# ME433.net
KiCad netlist of a schematic drawn in EAGLE
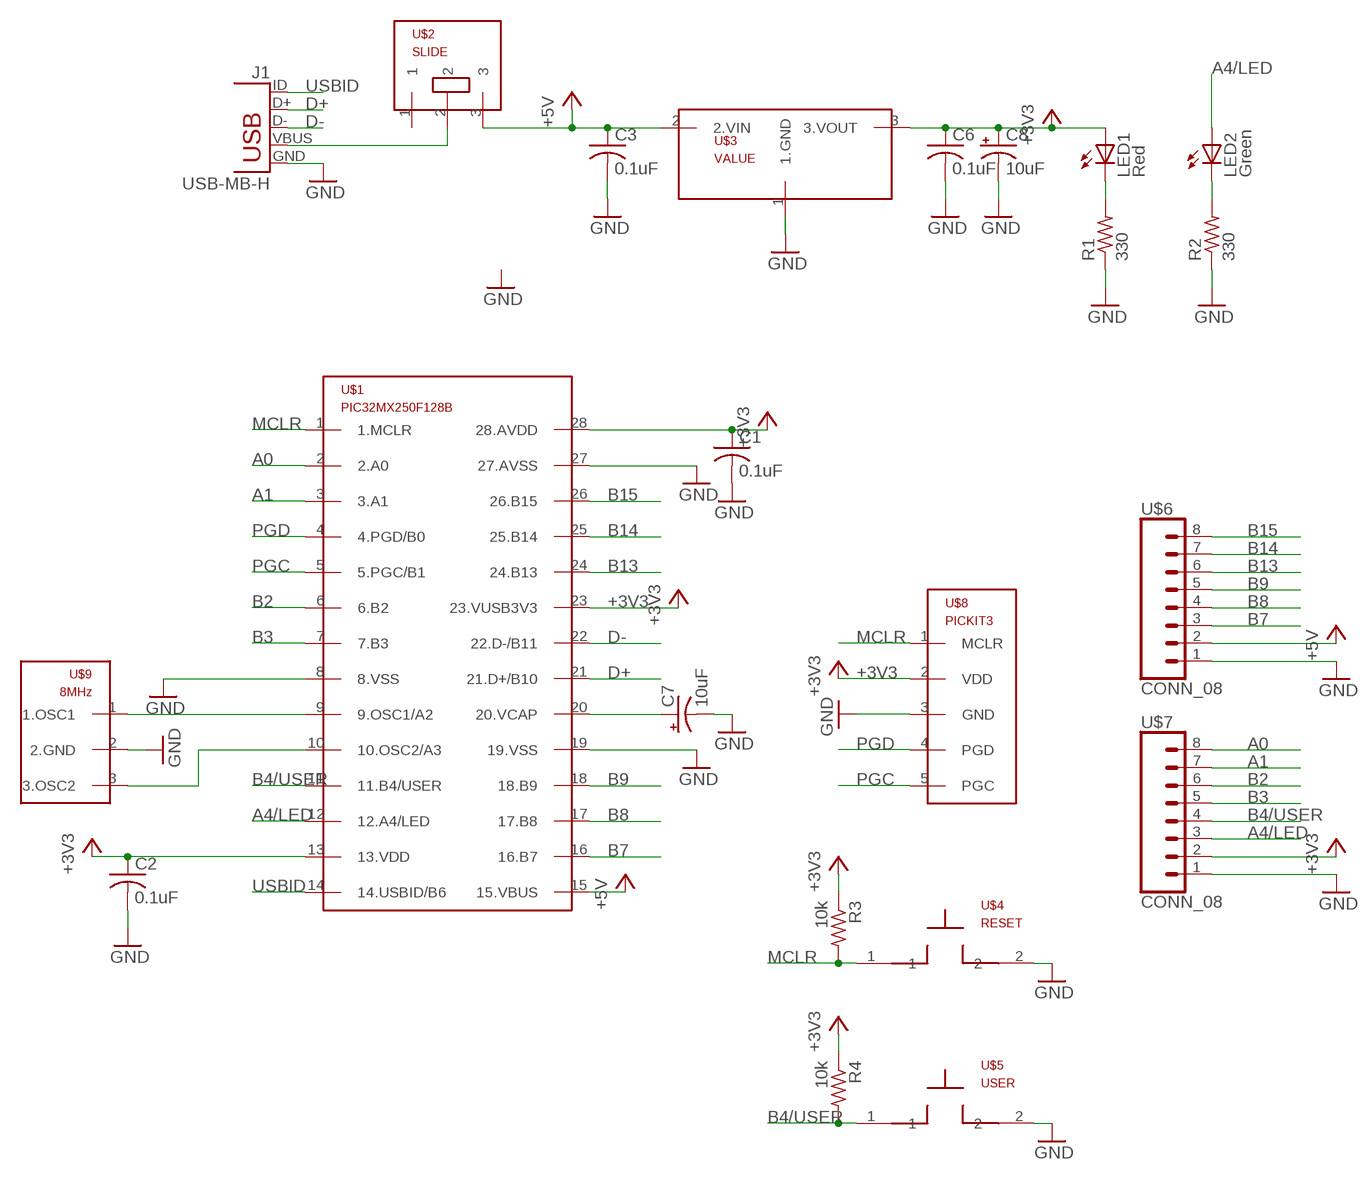
[diagram p0: schematic, sheet 1]

(export (version "E")
  (design (tool "Eeschema 10.0.6"))
  (components
    (comp (ref "C1")
      (value "0.1uF")
      (footprint "eagle-import:C025-025X050")
      (libsource (lib "eagle-import") (part "C-US025-025X050"))
    )
    (comp (ref "C2")
      (value "0.1uF")
      (footprint "eagle-import:C025-025X050")
      (libsource (lib "eagle-import") (part "C-US025-025X050"))
    )
    (comp (ref "C3")
      (value "0.1uF")
      (footprint "eagle-import:C025-025X050")
      (libsource (lib "eagle-import") (part "C-US025-025X050"))
    )
    (comp (ref "C6")
      (value "0.1uF")
      (footprint "eagle-import:C025-025X050")
      (libsource (lib "eagle-import") (part "C-US025-025X050"))
    )
    (comp (ref "C7")
      (value "10uF")
      (footprint "eagle-import:B45181B")
      (libsource (lib "eagle-import") (part "CPOL-USB45181B"))
    )
    (comp (ref "C8")
      (value "10uF")
      (footprint "eagle-import:B45181B")
      (libsource (lib "eagle-import") (part "CPOL-USB45181B"))
    )
    (comp (ref "J1")
      (value "USB-MB-H")
      (footprint "eagle-import:USB-MB-H")
      (libsource (lib "eagle-import") (part "USB-MB-H"))
    )
    (comp (ref "LED1")
      (value "Red")
      (footprint "eagle-import:LED3MM")
      (libsource (lib "eagle-import") (part "LED3MM"))
    )
    (comp (ref "LED2")
      (value "Green")
      (footprint "eagle-import:LED3MM")
      (libsource (lib "eagle-import") (part "LED3MM"))
    )
    (comp (ref "R1")
      (value "330")
      (footprint "eagle-import:0207_10")
      (libsource (lib "eagle-import") (part "R-US_0207/10"))
    )
    (comp (ref "R2")
      (value "330")
      (footprint "eagle-import:0207_10")
      (libsource (lib "eagle-import") (part "R-US_0207/10"))
    )
    (comp (ref "R3")
      (value "10k")
      (footprint "eagle-import:0207_10")
      (libsource (lib "eagle-import") (part "R-US_0207/10"))
    )
    (comp (ref "R4")
      (value "10k")
      (footprint "eagle-import:0207_10")
      (libsource (lib "eagle-import") (part "R-US_0207/10"))
    )
    (comp (ref "U$1")
      (value "PIC32MX250F128B")
      (footprint "eagle-import:DIL28-3")
      (libsource (lib "eagle-import") (part "PIC32MX250F128B"))
    )
    (comp (ref "U$2")
      (value "SLIDE")
      (footprint "eagle-import:SLIDE")
      (libsource (lib "eagle-import") (part "SLIDE"))
    )
    (comp (ref "U$3")
      (value "MCP1702")
      (footprint "eagle-import:TO92")
      (libsource (lib "eagle-import") (part "MCP1702"))
    )
    (comp (ref "U$4")
      (value "RESET")
      (footprint "eagle-import:PB")
      (libsource (lib "eagle-import") (part "PB"))
    )
    (comp (ref "U$5")
      (value "USER")
      (footprint "eagle-import:PB")
      (libsource (lib "eagle-import") (part "PB"))
    )
    (comp (ref "U$6")
      (value "CONN_08")
      (footprint "eagle-import:1X08")
      (libsource (lib "eagle-import") (part "CONN_08"))
    )
    (comp (ref "U$7")
      (value "CONN_08")
      (footprint "eagle-import:1X08")
      (libsource (lib "eagle-import") (part "CONN_08"))
    )
    (comp (ref "U$8")
      (value "PICKIT3")
      (footprint "eagle-import:1X05")
      (libsource (lib "eagle-import") (part "PICKIT3"))
    )
    (comp (ref "U$9")
      (value "8MHz")
      (footprint "eagle-import:OSC")
      (libsource (lib "eagle-import") (part "OSC"))
    )
  )
  (nets
    (net (code "1") (name "+3V3") (class "Default")
      (node (ref "C1") (pin "1") (pinfunction "1_1") (pintype "passive"))
      (node (ref "C2") (pin "1") (pinfunction "1_1") (pintype "passive"))
      (node (ref "C6") (pin "1") (pinfunction "1_1") (pintype "passive"))
      (node (ref "C8") (pin "+") (pinfunction "+_+") (pintype "passive"))
      (node (ref "LED1") (pin "A") (pinfunction "A_A") (pintype "passive"))
      (node (ref "R3") (pin "1") (pinfunction "1_1") (pintype "passive"))
      (node (ref "R4") (pin "1") (pinfunction "1_1") (pintype "passive"))
      (node (ref "U$1") (pin "13") (pinfunction "13.VDD_13") (pintype "bidirectional"))
      (node (ref "U$1") (pin "23") (pinfunction "23.VUSB3V3_23") (pintype "bidirectional"))
      (node (ref "U$1") (pin "28") (pinfunction "28.AVDD_28") (pintype "bidirectional"))
      (node (ref "U$3") (pin "3") (pinfunction "3.VOUT_3") (pintype "bidirectional"))
      (node (ref "U$7") (pin "2") (pinfunction "2_2") (pintype "passive"))
      (node (ref "U$8") (pin "2") (pinfunction "VDD_2") (pintype "bidirectional"))
    )
    (net (code "2") (name "+5V") (class "Default")
      (node (ref "C3") (pin "1") (pinfunction "1_1") (pintype "passive"))
      (node (ref "U$1") (pin "15") (pinfunction "15.VBUS_15") (pintype "bidirectional"))
      (node (ref "U$2") (pin "3") (pinfunction "3_3") (pintype "bidirectional"))
      (node (ref "U$3") (pin "2") (pinfunction "2.VIN_2") (pintype "bidirectional"))
      (node (ref "U$6") (pin "2") (pinfunction "2_2") (pintype "passive"))
    )
    (net (code "3") (name "/A0") (class "Default")
      (node (ref "U$1") (pin "2") (pinfunction "2.A0_2") (pintype "bidirectional"))
      (node (ref "U$7") (pin "8") (pinfunction "8_8") (pintype "passive"))
    )
    (net (code "4") (name "/A1") (class "Default")
      (node (ref "U$1") (pin "3") (pinfunction "3.A1_3") (pintype "bidirectional"))
      (node (ref "U$7") (pin "7") (pinfunction "7_7") (pintype "passive"))
    )
    (net (code "5") (name "/A4{slash}LED") (class "Default")
      (node (ref "LED2") (pin "A") (pinfunction "A_A") (pintype "passive"))
      (node (ref "U$1") (pin "12") (pinfunction "12.A4/LED_12") (pintype "bidirectional"))
      (node (ref "U$7") (pin "3") (pinfunction "3_3") (pintype "passive"))
    )
    (net (code "6") (name "/B2") (class "Default")
      (node (ref "U$1") (pin "6") (pinfunction "6.B2_6") (pintype "bidirectional"))
      (node (ref "U$7") (pin "6") (pinfunction "6_6") (pintype "passive"))
    )
    (net (code "7") (name "/B3") (class "Default")
      (node (ref "U$1") (pin "7") (pinfunction "7.B3_7") (pintype "bidirectional"))
      (node (ref "U$7") (pin "5") (pinfunction "5_5") (pintype "passive"))
    )
    (net (code "8") (name "/B4{slash}USER") (class "Default")
      (node (ref "R4") (pin "2") (pinfunction "2_2") (pintype "passive"))
      (node (ref "U$1") (pin "11") (pinfunction "11.B4/USER_11") (pintype "bidirectional"))
      (node (ref "U$5") (pin "1") (pinfunction "1_1") (pintype "bidirectional"))
      (node (ref "U$7") (pin "4") (pinfunction "4_4") (pintype "passive"))
    )
    (net (code "9") (name "/B7") (class "Default")
      (node (ref "U$1") (pin "16") (pinfunction "16.B7_16") (pintype "bidirectional"))
      (node (ref "U$6") (pin "3") (pinfunction "3_3") (pintype "passive"))
    )
    (net (code "10") (name "/B8") (class "Default")
      (node (ref "U$1") (pin "17") (pinfunction "17.B8_17") (pintype "bidirectional"))
      (node (ref "U$6") (pin "4") (pinfunction "4_4") (pintype "passive"))
    )
    (net (code "11") (name "/B9") (class "Default")
      (node (ref "U$1") (pin "18") (pinfunction "18.B9_18") (pintype "bidirectional"))
      (node (ref "U$6") (pin "5") (pinfunction "5_5") (pintype "passive"))
    )
    (net (code "12") (name "/B13") (class "Default")
      (node (ref "U$1") (pin "24") (pinfunction "24.B13_24") (pintype "bidirectional"))
      (node (ref "U$6") (pin "6") (pinfunction "6_6") (pintype "passive"))
    )
    (net (code "13") (name "/B14") (class "Default")
      (node (ref "U$1") (pin "25") (pinfunction "25.B14_25") (pintype "bidirectional"))
      (node (ref "U$6") (pin "7") (pinfunction "7_7") (pintype "passive"))
    )
    (net (code "14") (name "/B15") (class "Default")
      (node (ref "U$1") (pin "26") (pinfunction "26.B15_26") (pintype "bidirectional"))
      (node (ref "U$6") (pin "8") (pinfunction "8_8") (pintype "passive"))
    )
    (net (code "15") (name "/D+") (class "Default")
      (node (ref "J1") (pin "D+") (pinfunction "D+_D+") (pintype "bidirectional"))
      (node (ref "U$1") (pin "21") (pinfunction "21.D+/B10_21") (pintype "bidirectional"))
    )
    (net (code "16") (name "/D-") (class "Default")
      (node (ref "J1") (pin "D-") (pinfunction "D-_D-") (pintype "bidirectional"))
      (node (ref "U$1") (pin "22") (pinfunction "22.D-/B11_22") (pintype "bidirectional"))
    )
    (net (code "17") (name "/MCLR") (class "Default")
      (node (ref "R3") (pin "2") (pinfunction "2_2") (pintype "passive"))
      (node (ref "U$1") (pin "1") (pinfunction "1.MCLR_1") (pintype "bidirectional"))
      (node (ref "U$4") (pin "1") (pinfunction "1_1") (pintype "bidirectional"))
      (node (ref "U$8") (pin "1") (pinfunction "MCLR_1") (pintype "bidirectional"))
    )
    (net (code "18") (name "/PGC") (class "Default")
      (node (ref "U$1") (pin "5") (pinfunction "5.PGC/B1_5") (pintype "bidirectional"))
      (node (ref "U$8") (pin "5") (pinfunction "PGC_5") (pintype "bidirectional"))
    )
    (net (code "19") (name "/PGD") (class "Default")
      (node (ref "U$1") (pin "4") (pinfunction "4.PGD/B0_4") (pintype "bidirectional"))
      (node (ref "U$8") (pin "4") (pinfunction "PGD_4") (pintype "bidirectional"))
    )
    (net (code "20") (name "/USBID") (class "Default")
      (node (ref "J1") (pin "ID") (pinfunction "D+1_ID") (pintype "bidirectional"))
      (node (ref "U$1") (pin "14") (pinfunction "14.USBID/B6_14") (pintype "bidirectional"))
    )
    (net (code "21") (name "GND") (class "Default")
      (node (ref "C1") (pin "2") (pinfunction "2_2") (pintype "passive"))
      (node (ref "C2") (pin "2") (pinfunction "2_2") (pintype "passive"))
      (node (ref "C3") (pin "2") (pinfunction "2_2") (pintype "passive"))
      (node (ref "C6") (pin "2") (pinfunction "2_2") (pintype "passive"))
      (node (ref "C7") (pin "-") (pinfunction "-_-") (pintype "passive"))
      (node (ref "C8") (pin "-") (pinfunction "-_-") (pintype "passive"))
      (node (ref "J1") (pin "GND") (pinfunction "GND_GND") (pintype "bidirectional"))
      (node (ref "R1") (pin "1") (pinfunction "1_1") (pintype "passive"))
      (node (ref "R2") (pin "1") (pinfunction "1_1") (pintype "passive"))
      (node (ref "U$1") (pin "19") (pinfunction "19.VSS_19") (pintype "bidirectional"))
      (node (ref "U$1") (pin "27") (pinfunction "27.AVSS_27") (pintype "bidirectional"))
      (node (ref "U$1") (pin "8") (pinfunction "8.VSS_8") (pintype "bidirectional"))
      (node (ref "U$3") (pin "1") (pinfunction "1.GND_1") (pintype "bidirectional"))
      (node (ref "U$4") (pin "2") (pinfunction "2_2") (pintype "bidirectional"))
      (node (ref "U$5") (pin "2") (pinfunction "2_2") (pintype "bidirectional"))
      (node (ref "U$6") (pin "1") (pinfunction "1_1") (pintype "passive"))
      (node (ref "U$7") (pin "1") (pinfunction "1_1") (pintype "passive"))
      (node (ref "U$8") (pin "3") (pinfunction "GND_3") (pintype "bidirectional"))
      (node (ref "U$9") (pin "2") (pinfunction "2.GND_2") (pintype "bidirectional"))
    )
    (net (code "22") (name "Net-(J1-PadVBUS)") (class "Default")
      (node (ref "J1") (pin "VBUS") (pinfunction "VBUS_VBUS") (pintype "bidirectional"))
      (node (ref "U$2") (pin "2") (pinfunction "2_2") (pintype "bidirectional"))
    )
    (net (code "23") (name "Net-(LED1-C)") (class "Default")
      (node (ref "LED1") (pin "K") (pinfunction "C_K") (pintype "passive"))
      (node (ref "R1") (pin "2") (pinfunction "2_2") (pintype "passive"))
    )
    (net (code "24") (name "Net-(LED2-C)") (class "Default")
      (node (ref "LED2") (pin "K") (pinfunction "C_K") (pintype "passive"))
      (node (ref "R2") (pin "2") (pinfunction "2_2") (pintype "passive"))
    )
    (net (code "25") (name "Net-(U$1-9.OSC1{slash}A2)") (class "Default")
      (node (ref "U$1") (pin "9") (pinfunction "9.OSC1/A2_9") (pintype "bidirectional"))
      (node (ref "U$9") (pin "1") (pinfunction "1.OSC1_1") (pintype "bidirectional"))
    )
    (net (code "26") (name "Net-(U$1-10.OSC2{slash}A3)") (class "Default")
      (node (ref "U$1") (pin "10") (pinfunction "10.OSC2/A3_10") (pintype "bidirectional"))
      (node (ref "U$9") (pin "3") (pinfunction "3.OSC2_3") (pintype "bidirectional"))
    )
    (net (code "27") (name "Net-(U$1-20.VCAP)") (class "Default")
      (node (ref "C7") (pin "+") (pinfunction "+_+") (pintype "passive"))
      (node (ref "U$1") (pin "20") (pinfunction "20.VCAP_20") (pintype "bidirectional"))
    )
    (net (code "28") (name "unconnected-(U$2-Pad1)") (class "Default")
      (node (ref "U$2") (pin "1") (pinfunction "1_1") (pintype "bidirectional"))
    )
  )
)
